# SCP.net
KiCad netlist of a schematic drawn in Altium Designer
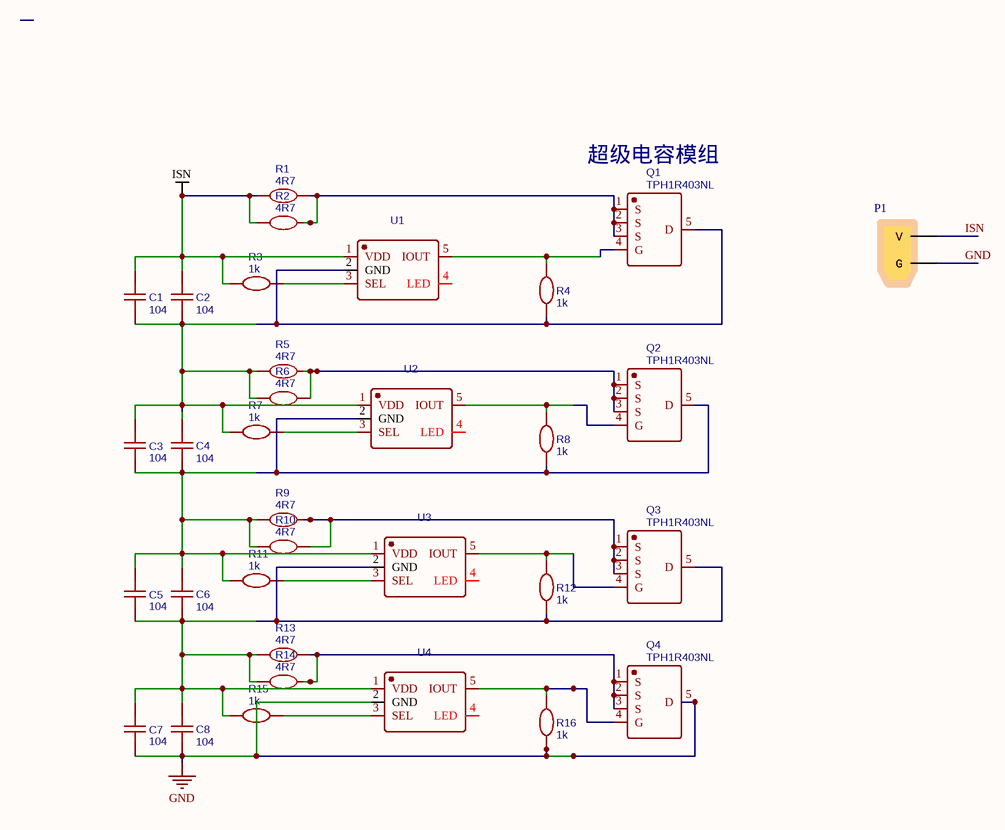
[diagram p0: SCP.SchDoc]

(export (version "E")
  (design (tool "Eeschema 10.0.6"))
  (components
    (comp (ref "C1")
      (value "104")
      (footprint "C0805")
      (fields (field (name "CONTRIBUTOR") "LCEDA_Lib"))
      (libsource (lib "altium-import") (part "root_1_104_"))
    )
    (comp (ref "C2")
      (value "104")
      (footprint "PCBComponent_1 - duplicate")
      (fields (field (name "CONTRIBUTOR") "LCEDA_Lib"))
      (libsource (lib "altium-import") (part "root_1_104_"))
    )
    (comp (ref "C3")
      (value "104")
      (footprint "C0805")
      (fields (field (name "CONTRIBUTOR") "LCEDA_Lib"))
      (libsource (lib "altium-import") (part "root_1_104_"))
    )
    (comp (ref "C4")
      (value "104")
      (footprint "PCBComponent_1 - duplicate")
      (fields (field (name "CONTRIBUTOR") "LCEDA_Lib"))
      (libsource (lib "altium-import") (part "root_1_104_"))
    )
    (comp (ref "C5")
      (value "104")
      (footprint "C0805")
      (fields (field (name "CONTRIBUTOR") "LCEDA_Lib"))
      (libsource (lib "altium-import") (part "root_1_104_"))
    )
    (comp (ref "C6")
      (value "104")
      (footprint "PCBComponent_1 - duplicate")
      (fields (field (name "CONTRIBUTOR") "LCEDA_Lib"))
      (libsource (lib "altium-import") (part "root_1_104_"))
    )
    (comp (ref "C7")
      (value "104")
      (footprint "全套封装:C0805")
      (fields (field (name "CONTRIBUTOR") "LCEDA_Lib"))
      (libsource (lib "altium-import") (part "root_1_104_"))
    )
    (comp (ref "C8")
      (value "104")
      (footprint "PCBComponent_1 - duplicate")
      (fields (field (name "CONTRIBUTOR") "LCEDA_Lib"))
      (libsource (lib "altium-import") (part "root_1_104_"))
    )
    (comp (ref "P1")
      (value "~")
      (footprint "XT30 DIP")
      (description "XT30 板载直头直插")
      (libsource (lib "car bottom") (part "XT30 DIP"))
    )
    (comp (ref "Q1")
      (value "TPH1R403NL")
      (footprint "POWERVDFN-8_L6.2-W5.2-P1.27-LS6.0-BL")
      (fields (field (name "BOM_SUPPLIER PART") "C83440"))
      (libsource (lib "altium-import") (part "root_0_TPH1R403NL_"))
    )
    (comp (ref "Q2")
      (value "TPH1R403NL")
      (footprint "POWERVDFN-8_L6.2-W5.2-P1.27-LS6.0-BL")
      (fields (field (name "BOM_SUPPLIER PART") "C83440"))
      (libsource (lib "altium-import") (part "root_0_TPH1R403NL_"))
    )
    (comp (ref "Q3")
      (value "TPH1R403NL")
      (footprint "POWERVDFN-8_L6.2-W5.2-P1.27-LS6.0-BL")
      (fields (field (name "BOM_SUPPLIER PART") "C83440"))
      (libsource (lib "altium-import") (part "root_0_TPH1R403NL_"))
    )
    (comp (ref "Q4")
      (value "TPH1R403NL")
      (footprint "POWERVDFN-8_L6.2-W5.2-P1.27-LS6.0-BL")
      (fields (field (name "BOM_SUPPLIER PART") "C83440"))
      (libsource (lib "altium-import") (part "root_0_TPH1R403NL_"))
    )
    (comp (ref "R1")
      (value "4R7")
      (footprint "R2512 1")
      (fields
        (field (name "BOM_SUPPLIER PART") "C413739")
        (field (name "BOM_MANUFACTURER PART") "ERJPB6B4701V")
        (field (name "CONTRIBUTOR") "LCSC")
      )
      (libsource (lib "altium-import") (part "root_0_4R7_"))
    )
    (comp (ref "R2")
      (value "4R7")
      (footprint "R2512 1")
      (fields
        (field (name "BOM_SUPPLIER PART") "C413739")
        (field (name "BOM_MANUFACTURER PART") "ERJPB6B4701V")
        (field (name "CONTRIBUTOR") "LCSC")
      )
      (libsource (lib "altium-import") (part "root_0_4R7_"))
    )
    (comp (ref "R3")
      (value "1k")
      (footprint "R0603")
      (fields (field (name "CONTRIBUTOR") "LCEDA_Lib"))
      (libsource (lib "altium-import") (part "root_2_1k_"))
    )
    (comp (ref "R4")
      (value "1k")
      (footprint "R0603")
      (fields (field (name "CONTRIBUTOR") "LCEDA_Lib"))
      (libsource (lib "altium-import") (part "root_1_1k_"))
    )
    (comp (ref "R5")
      (value "4R7")
      (footprint "R2512 1")
      (fields
        (field (name "BOM_SUPPLIER PART") "C413739")
        (field (name "BOM_MANUFACTURER PART") "ERJPB6B4701V")
        (field (name "CONTRIBUTOR") "LCSC")
      )
      (libsource (lib "altium-import") (part "root_0_4R7_"))
    )
    (comp (ref "R6")
      (value "4R7")
      (footprint "R2512 1")
      (fields
        (field (name "BOM_SUPPLIER PART") "C413739")
        (field (name "BOM_MANUFACTURER PART") "ERJPB6B4701V")
        (field (name "CONTRIBUTOR") "LCSC")
      )
      (libsource (lib "altium-import") (part "root_0_4R7_"))
    )
    (comp (ref "R7")
      (value "1k")
      (footprint "R0603")
      (fields (field (name "CONTRIBUTOR") "LCEDA_Lib"))
      (libsource (lib "altium-import") (part "root_2_1k_"))
    )
    (comp (ref "R8")
      (value "1k")
      (footprint "R0603")
      (fields (field (name "CONTRIBUTOR") "LCEDA_Lib"))
      (libsource (lib "altium-import") (part "root_1_1k_"))
    )
    (comp (ref "R9")
      (value "4R7")
      (footprint "R2512 1")
      (fields
        (field (name "BOM_SUPPLIER PART") "C413739")
        (field (name "BOM_MANUFACTURER PART") "ERJPB6B4701V")
        (field (name "CONTRIBUTOR") "LCSC")
      )
      (libsource (lib "altium-import") (part "root_0_4R7_"))
    )
    (comp (ref "R10")
      (value "4R7")
      (footprint "R2512 1")
      (fields
        (field (name "BOM_SUPPLIER PART") "C413739")
        (field (name "BOM_MANUFACTURER PART") "ERJPB6B4701V")
        (field (name "CONTRIBUTOR") "LCSC")
      )
      (libsource (lib "altium-import") (part "root_0_4R7_"))
    )
    (comp (ref "R11")
      (value "1k")
      (footprint "R0603")
      (fields (field (name "CONTRIBUTOR") "LCEDA_Lib"))
      (libsource (lib "altium-import") (part "root_2_1k_"))
    )
    (comp (ref "R12")
      (value "1k")
      (footprint "R0603")
      (fields (field (name "CONTRIBUTOR") "LCEDA_Lib"))
      (libsource (lib "altium-import") (part "root_1_1k_"))
    )
    (comp (ref "R13")
      (value "4R7")
      (footprint "R2512 1")
      (fields
        (field (name "BOM_SUPPLIER PART") "C413739")
        (field (name "BOM_MANUFACTURER PART") "ERJPB6B4701V")
        (field (name "CONTRIBUTOR") "LCSC")
      )
      (libsource (lib "altium-import") (part "root_0_4R7_"))
    )
    (comp (ref "R14")
      (value "4R7")
      (footprint "R2512 1")
      (fields
        (field (name "BOM_SUPPLIER PART") "C413739")
        (field (name "BOM_MANUFACTURER PART") "ERJPB6B4701V")
        (field (name "CONTRIBUTOR") "LCSC")
      )
      (libsource (lib "altium-import") (part "root_0_4R7_"))
    )
    (comp (ref "R15")
      (value "1k")
      (footprint "R0603")
      (fields (field (name "CONTRIBUTOR") "LCEDA_Lib"))
      (libsource (lib "altium-import") (part "root_2_1k_"))
    )
    (comp (ref "R16")
      (value "1k")
      (footprint "R0603")
      (fields (field (name "CONTRIBUTOR") "LCEDA_Lib"))
      (libsource (lib "altium-import") (part "root_1_1k_"))
    )
    (comp (ref "U1")
      (value "~")
      (footprint "TSOT-23-5_L2.9-W1.6-P0.95-LS2.8-BL")
      (fields
        (field (name "BOM_MANUFACTURER PART") "00")
        (field (name "BOM_SUPPLIER PART") "0000")
        (field (name "CONTRIBUTOR") "futuresailor")
      )
      (libsource (lib "Supercapacitor") (part "BW6101"))
    )
    (comp (ref "U2")
      (value "~")
      (footprint "TSOT-23-5_L2.9-W1.6-P0.95-LS2.8-BL")
      (fields (field (name "CONTRIBUTOR") "futuresailor"))
      (libsource (lib "foot") (part "BW6101"))
    )
    (comp (ref "U3")
      (value "~")
      (footprint "TSOT-23-5_L2.9-W1.6-P0.95-LS2.8-BL")
      (fields
        (field (name "BOM_MANUFACTURER PART") "00")
        (field (name "BOM_SUPPLIER PART") "0000")
        (field (name "CONTRIBUTOR") "futuresailor")
      )
      (libsource (lib "Supercapacitor") (part "BW6101"))
    )
    (comp (ref "U4")
      (value "~")
      (footprint "TSOT-23-5_L2.9-W1.6-P0.95-LS2.8-BL")
      (fields
        (field (name "BOM_MANUFACTURER PART") "00")
        (field (name "BOM_SUPPLIER PART") "0000")
        (field (name "CONTRIBUTOR") "futuresailor")
      )
      (libsource (lib "Supercapacitor") (part "BW6101"))
    )
  )
  (nets
    (net (code "1") (name "GND") (class "Default")
      (node (ref "C7") (pin "1") (pinfunction "1_1") (pintype "passive"))
      (node (ref "C8") (pin "1") (pinfunction "1_1") (pintype "passive"))
      (node (ref "P1") (pin "2") (pinfunction "G_2") (pintype "passive"))
      (node (ref "Q4") (pin "5") (pinfunction "D_5") (pintype "passive"))
      (node (ref "R16") (pin "1") (pinfunction "1_1") (pintype "passive"))
      (node (ref "U4") (pin "2") (pinfunction "GND_2") (pintype "passive"))
    )
    (net (code "2") (name "ISN") (class "Default")
      (node (ref "C1") (pin "2") (pinfunction "2_2") (pintype "passive"))
      (node (ref "C2") (pin "2") (pinfunction "2_2") (pintype "passive"))
      (node (ref "P1") (pin "1") (pinfunction "V_1") (pintype "passive"))
      (node (ref "R1") (pin "1") (pinfunction "1_1") (pintype "passive"))
      (node (ref "R2") (pin "1") (pinfunction "1_1") (pintype "passive"))
      (node (ref "R3") (pin "2") (pinfunction "2_2") (pintype "passive"))
      (node (ref "U1") (pin "1") (pinfunction "VDD_1") (pintype "passive"))
    )
    (net (code "3") (name "Net-(Q1-D)") (class "Default")
      (node (ref "C1") (pin "1") (pinfunction "1_1") (pintype "passive"))
      (node (ref "C2") (pin "1") (pinfunction "1_1") (pintype "passive"))
      (node (ref "C3") (pin "2") (pinfunction "2_2") (pintype "passive"))
      (node (ref "C4") (pin "2") (pinfunction "2_2") (pintype "passive"))
      (node (ref "Q1") (pin "5") (pinfunction "D_5") (pintype "passive"))
      (node (ref "R4") (pin "1") (pinfunction "1_1") (pintype "passive"))
      (node (ref "R5") (pin "1") (pinfunction "1_1") (pintype "passive"))
      (node (ref "R6") (pin "1") (pinfunction "1_1") (pintype "passive"))
      (node (ref "R7") (pin "2") (pinfunction "2_2") (pintype "passive"))
      (node (ref "U1") (pin "2") (pinfunction "GND_2") (pintype "passive"))
      (node (ref "U2") (pin "1") (pinfunction "VDD_1") (pintype "passive"))
    )
    (net (code "4") (name "Net-(Q1-G)") (class "Default")
      (node (ref "Q1") (pin "4") (pinfunction "G_4") (pintype "passive"))
      (node (ref "R4") (pin "2") (pinfunction "2_2") (pintype "passive"))
      (node (ref "U1") (pin "5") (pinfunction "IOUT_5") (pintype "passive"))
    )
    (net (code "5") (name "Net-(Q1-S-Pad1)") (class "Default")
      (node (ref "Q1") (pin "1") (pinfunction "S_1") (pintype "passive"))
      (node (ref "Q1") (pin "2") (pinfunction "S_2") (pintype "passive"))
      (node (ref "Q1") (pin "3") (pinfunction "S_3") (pintype "passive"))
      (node (ref "R1") (pin "2") (pinfunction "2_2") (pintype "passive"))
      (node (ref "R2") (pin "2") (pinfunction "2_2") (pintype "passive"))
    )
    (net (code "6") (name "Net-(Q2-D)") (class "Default")
      (node (ref "C3") (pin "1") (pinfunction "1_1") (pintype "passive"))
      (node (ref "C4") (pin "1") (pinfunction "1_1") (pintype "passive"))
      (node (ref "C5") (pin "2") (pinfunction "2_2") (pintype "passive"))
      (node (ref "C6") (pin "2") (pinfunction "2_2") (pintype "passive"))
      (node (ref "Q2") (pin "5") (pinfunction "D_5") (pintype "passive"))
      (node (ref "R10") (pin "1") (pinfunction "1_1") (pintype "passive"))
      (node (ref "R11") (pin "2") (pinfunction "2_2") (pintype "passive"))
      (node (ref "R8") (pin "1") (pinfunction "1_1") (pintype "passive"))
      (node (ref "R9") (pin "1") (pinfunction "1_1") (pintype "passive"))
      (node (ref "U2") (pin "2") (pinfunction "GND_2") (pintype "passive"))
      (node (ref "U3") (pin "1") (pinfunction "VDD_1") (pintype "passive"))
    )
    (net (code "7") (name "Net-(Q2-G)") (class "Default")
      (node (ref "Q2") (pin "4") (pinfunction "G_4") (pintype "passive"))
      (node (ref "R8") (pin "2") (pinfunction "2_2") (pintype "passive"))
      (node (ref "U2") (pin "5") (pinfunction "IOUT_5") (pintype "passive"))
    )
    (net (code "8") (name "Net-(Q2-S-Pad1)") (class "Default")
      (node (ref "Q2") (pin "1") (pinfunction "S_1") (pintype "passive"))
      (node (ref "Q2") (pin "2") (pinfunction "S_2") (pintype "passive"))
      (node (ref "Q2") (pin "3") (pinfunction "S_3") (pintype "passive"))
      (node (ref "R5") (pin "2") (pinfunction "2_2") (pintype "passive"))
      (node (ref "R6") (pin "2") (pinfunction "2_2") (pintype "passive"))
    )
    (net (code "9") (name "Net-(Q3-D)") (class "Default")
      (node (ref "C5") (pin "1") (pinfunction "1_1") (pintype "passive"))
      (node (ref "C6") (pin "1") (pinfunction "1_1") (pintype "passive"))
      (node (ref "C7") (pin "2") (pinfunction "2_2") (pintype "passive"))
      (node (ref "C8") (pin "2") (pinfunction "2_2") (pintype "passive"))
      (node (ref "Q3") (pin "5") (pinfunction "D_5") (pintype "passive"))
      (node (ref "R12") (pin "1") (pinfunction "1_1") (pintype "passive"))
      (node (ref "R13") (pin "1") (pinfunction "1_1") (pintype "passive"))
      (node (ref "R14") (pin "1") (pinfunction "1_1") (pintype "passive"))
      (node (ref "R15") (pin "2") (pinfunction "2_2") (pintype "passive"))
      (node (ref "U3") (pin "2") (pinfunction "GND_2") (pintype "passive"))
      (node (ref "U4") (pin "1") (pinfunction "VDD_1") (pintype "passive"))
    )
    (net (code "10") (name "Net-(Q3-G)") (class "Default")
      (node (ref "Q3") (pin "4") (pinfunction "G_4") (pintype "passive"))
      (node (ref "R12") (pin "2") (pinfunction "2_2") (pintype "passive"))
      (node (ref "U3") (pin "5") (pinfunction "IOUT_5") (pintype "passive"))
    )
    (net (code "11") (name "Net-(Q3-S-Pad1)") (class "Default")
      (node (ref "Q3") (pin "1") (pinfunction "S_1") (pintype "passive"))
      (node (ref "Q3") (pin "2") (pinfunction "S_2") (pintype "passive"))
      (node (ref "Q3") (pin "3") (pinfunction "S_3") (pintype "passive"))
      (node (ref "R10") (pin "2") (pinfunction "2_2") (pintype "passive"))
      (node (ref "R9") (pin "2") (pinfunction "2_2") (pintype "passive"))
    )
    (net (code "12") (name "Net-(Q4-G)") (class "Default")
      (node (ref "Q4") (pin "4") (pinfunction "G_4") (pintype "passive"))
      (node (ref "R16") (pin "2") (pinfunction "2_2") (pintype "passive"))
      (node (ref "U4") (pin "5") (pinfunction "IOUT_5") (pintype "passive"))
    )
    (net (code "13") (name "Net-(Q4-S-Pad1)") (class "Default")
      (node (ref "Q4") (pin "1") (pinfunction "S_1") (pintype "passive"))
      (node (ref "Q4") (pin "2") (pinfunction "S_2") (pintype "passive"))
      (node (ref "Q4") (pin "3") (pinfunction "S_3") (pintype "passive"))
      (node (ref "R13") (pin "2") (pinfunction "2_2") (pintype "passive"))
      (node (ref "R14") (pin "2") (pinfunction "2_2") (pintype "passive"))
    )
    (net (code "14") (name "Net-(U1-SEL)") (class "Default")
      (node (ref "R3") (pin "1") (pinfunction "1_1") (pintype "passive"))
      (node (ref "U1") (pin "3") (pinfunction "SEL_3") (pintype "passive"))
    )
    (net (code "15") (name "Net-(U2-SEL)") (class "Default")
      (node (ref "R7") (pin "1") (pinfunction "1_1") (pintype "passive"))
      (node (ref "U2") (pin "3") (pinfunction "SEL_3") (pintype "passive"))
    )
    (net (code "16") (name "Net-(U3-SEL)") (class "Default")
      (node (ref "R11") (pin "1") (pinfunction "1_1") (pintype "passive"))
      (node (ref "U3") (pin "3") (pinfunction "SEL_3") (pintype "passive"))
    )
    (net (code "17") (name "Net-(U4-SEL)") (class "Default")
      (node (ref "R15") (pin "1") (pinfunction "1_1") (pintype "passive"))
      (node (ref "U4") (pin "3") (pinfunction "SEL_3") (pintype "passive"))
    )
    (net (code "18") (name "unconnected-(U1-LED-Pad4)") (class "Default")
      (node (ref "U1") (pin "4") (pinfunction "LED_4") (pintype "passive"))
    )
    (net (code "19") (name "unconnected-(U2-LED-Pad4)") (class "Default")
      (node (ref "U2") (pin "4") (pinfunction "LED_4") (pintype "passive"))
    )
    (net (code "20") (name "unconnected-(U3-LED-Pad4)") (class "Default")
      (node (ref "U3") (pin "4") (pinfunction "LED_4") (pintype "passive"))
    )
    (net (code "21") (name "unconnected-(U4-LED-Pad4)") (class "Default")
      (node (ref "U4") (pin "4") (pinfunction "LED_4") (pintype "passive"))
    )
  )
)
